# MotorSheet.net
KiCad netlist of a schematic drawn in Altium Designer
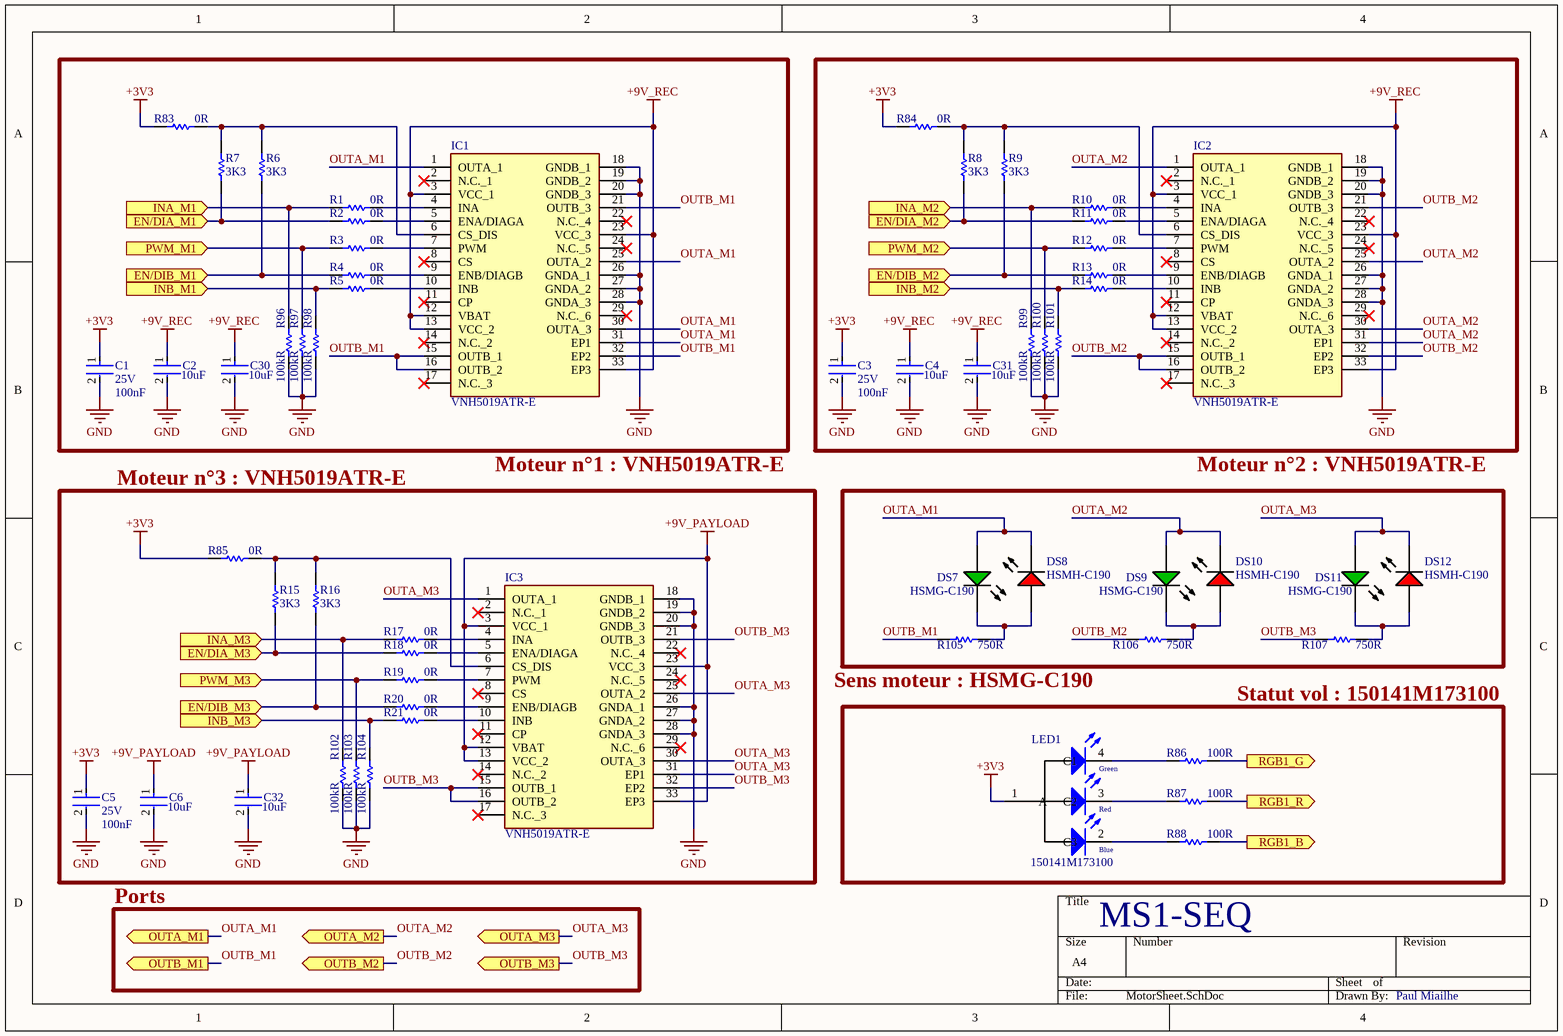
[diagram p0: MotorSheet.SchDoc]

(export (version "E")
  (design (tool "Eeschema 10.0.6"))
  (components
    (comp (ref "C1")
      (value "CGA3E2X7R1E104K080AA")
      (footprint "FP-CGA3E-0_3-0_1-MFG")
      (description "Cap Ceramic 100nF 25V X7R 10% Pad SMD 0603 +125°C Automotive T/R")
      (fields
        (field (name "VOLTAGE RATING (DC)") "25V")
        (field (name "CAPACITANCE") "100nF")
        (field (name "TOLERANCE") "10%")
        (field (name "MANUFACTURER") "TDK")
      )
      (libsource (lib "Altium Content Vault") (part "b4654b650e69147ec39a6b967a45e02"))
    )
    (comp (ref "C2")
      (value "GRM31CR71E106KA12L")
      (footprint "FP-GRM31C-0_2-e0_3_0_8-MFG")
      (description "Chip Multilayer Ceramic Capacitors for General Purpose, 1206, 10uF, X7R, 15%, 10%, 25V")
      (fields
        (field (name "TOLERANCE") "10%")
        (field (name "VOLTAGE") "25V")
        (field (name "CAPACITANCE") "10uF")
      )
      (libsource (lib "Altium Content Vault") (part "02cd4be3c70576c341d710602a673aa"))
    )
    (comp (ref "C3")
      (value "CGA3E2X7R1E104K080AA")
      (footprint "FP-CGA3E-0_3-0_1-MFG")
      (description "Cap Ceramic 100nF 25V X7R 10% Pad SMD 0603 +125°C Automotive T/R")
      (fields
        (field (name "VOLTAGE RATING (DC)") "25V")
        (field (name "CAPACITANCE") "100nF")
        (field (name "TOLERANCE") "10%")
        (field (name "MANUFACTURER") "TDK")
      )
      (libsource (lib "Altium Content Vault") (part "b4654b650e69147ec39a6b967a45e02"))
    )
    (comp (ref "C4")
      (value "GRM31CR71E106KA12L")
      (footprint "FP-GRM31C-0_2-e0_3_0_8-MFG")
      (description "Chip Multilayer Ceramic Capacitors for General Purpose, 1206, 10uF, X7R, 15%, 10%, 25V")
      (fields
        (field (name "TOLERANCE") "10%")
        (field (name "VOLTAGE") "25V")
        (field (name "CAPACITANCE") "10uF")
      )
      (libsource (lib "Altium Content Vault") (part "02cd4be3c70576c341d710602a673aa"))
    )
    (comp (ref "C5")
      (value "CGA3E2X7R1E104K080AA")
      (footprint "FP-CGA3E-0_3-0_1-MFG")
      (description "Cap Ceramic 100nF 25V X7R 10% Pad SMD 0603 +125°C Automotive T/R")
      (fields
        (field (name "VOLTAGE RATING (DC)") "25V")
        (field (name "CAPACITANCE") "100nF")
        (field (name "TOLERANCE") "10%")
        (field (name "MANUFACTURER") "TDK")
      )
      (libsource (lib "Altium Content Vault") (part "b4654b650e69147ec39a6b967a45e02"))
    )
    (comp (ref "C6")
      (value "GRM31CR71E106KA12L")
      (footprint "FP-GRM31C-0_2-e0_3_0_8-MFG")
      (description "Chip Multilayer Ceramic Capacitors for General Purpose, 1206, 10uF, X7R, 15%, 10%, 25V")
      (fields
        (field (name "TOLERANCE") "10%")
        (field (name "VOLTAGE") "25V")
        (field (name "CAPACITANCE") "10uF")
      )
      (libsource (lib "Altium Content Vault") (part "02cd4be3c70576c341d710602a673aa"))
    )
    (comp (ref "C30")
      (value "GRM31CR71E106KA12L")
      (footprint "FP-GRM31C-0_2-e0_3_0_8-MFG")
      (description "Chip Multilayer Ceramic Capacitors for General Purpose, 1206, 10uF, X7R, 15%, 10%, 25V")
      (fields
        (field (name "TOLERANCE") "10%")
        (field (name "VOLTAGE") "25V")
        (field (name "CAPACITANCE") "10uF")
      )
      (libsource (lib "Altium Content Vault") (part "02cd4be3c70576c341d710602a673aa"))
    )
    (comp (ref "C31")
      (value "GRM31CR71E106KA12L")
      (footprint "FP-GRM31C-0_2-e0_3_0_8-MFG")
      (description "Chip Multilayer Ceramic Capacitors for General Purpose, 1206, 10uF, X7R, 15%, 10%, 25V")
      (fields
        (field (name "TOLERANCE") "10%")
        (field (name "VOLTAGE") "25V")
        (field (name "CAPACITANCE") "10uF")
      )
      (libsource (lib "Altium Content Vault") (part "02cd4be3c70576c341d710602a673aa"))
    )
    (comp (ref "C32")
      (value "GRM31CR71E106KA12L")
      (footprint "FP-GRM31C-0_2-e0_3_0_8-MFG")
      (description "Chip Multilayer Ceramic Capacitors for General Purpose, 1206, 10uF, X7R, 15%, 10%, 25V")
      (fields
        (field (name "TOLERANCE") "10%")
        (field (name "VOLTAGE") "25V")
        (field (name "CAPACITANCE") "10uF")
      )
      (libsource (lib "Altium Content Vault") (part "02cd4be3c70576c341d710602a673aa"))
    )
    (comp (ref "DS7")
      (value "HSMG-C190")
      (footprint "AVAG-HSMX-C190_V")
      (description "Chip LED, Green, 2.2 V, -40 to 85 degC, 2-Pin SMD, RoHS, Tape and Reel")
      (libsource (lib "Altium Content Vault") (part "LED-GREEN-AK-2"))
    )
    (comp (ref "DS8")
      (value "HSMH-C190")
      (footprint "AVAG-HSMX-C190_V")
      (description "LED Uni-Color Red, 65 mW, 20 mA, -40 to 85 degC, 2-Pin SMD, RoHS, Tape and Reel")
      (libsource (lib "Altium Content Vault") (part "LED-RED-AK-2"))
    )
    (comp (ref "DS9")
      (value "HSMG-C190")
      (footprint "AVAG-HSMX-C190_V")
      (description "Chip LED, Green, 2.2 V, -40 to 85 degC, 2-Pin SMD, RoHS, Tape and Reel")
      (libsource (lib "Altium Content Vault") (part "LED-GREEN-AK-2"))
    )
    (comp (ref "DS10")
      (value "HSMH-C190")
      (footprint "AVAG-HSMX-C190_V")
      (description "LED Uni-Color Red, 65 mW, 20 mA, -40 to 85 degC, 2-Pin SMD, RoHS, Tape and Reel")
      (libsource (lib "Altium Content Vault") (part "LED-RED-AK-2"))
    )
    (comp (ref "DS11")
      (value "HSMG-C190")
      (footprint "AVAG-HSMX-C190_V")
      (description "Chip LED, Green, 2.2 V, -40 to 85 degC, 2-Pin SMD, RoHS, Tape and Reel")
      (libsource (lib "Altium Content Vault") (part "LED-GREEN-AK-2"))
    )
    (comp (ref "DS12")
      (value "HSMH-C190")
      (footprint "AVAG-HSMX-C190_V")
      (description "LED Uni-Color Red, 65 mW, 20 mA, -40 to 85 degC, 2-Pin SMD, RoHS, Tape and Reel")
      (libsource (lib "Altium Content Vault") (part "LED-RED-AK-2"))
    )
    (comp (ref "IC1")
      (value "VNH5019ATR-E")
      (footprint "SamacSys:VNH5019A-E_1")
      (description "Integrated Circuit")
      (fields (field (name "MOUSER PART NUMBER") "511-VNH5019ATR-E"))
      (libsource (lib "*") (part "VNH5019ATR-E"))
    )
    (comp (ref "IC2")
      (value "VNH5019ATR-E")
      (footprint "SamacSys:VNH5019A-E_1")
      (description "Integrated Circuit")
      (fields (field (name "MOUSER PART NUMBER") "511-VNH5019ATR-E"))
      (libsource (lib "*") (part "VNH5019ATR-E"))
    )
    (comp (ref "IC3")
      (value "VNH5019ATR-E")
      (footprint "SamacSys:VNH5019A-E_1")
      (description "Integrated Circuit")
      (fields (field (name "MOUSER PART NUMBER") "511-VNH5019ATR-E"))
      (libsource (lib "*") (part "VNH5019ATR-E"))
    )
    (comp (ref "LED1")
      (value "150141M173100")
      (footprint "3528_A")
      (description "SMD Full-Color Top LED, WL-SFTW, Red & Green & Blue")
      (fields (field (name "MANUFACTURER") "Wuerth Elektronik"))
      (libsource (lib "Altium Content Vault") (part "WE-LED_RGB_A1B2R3G4-4"))
    )
    (comp (ref "R1")
      (value "0R")
      (footprint "RESC1608X55X25ML10T15")
      (description "Chip Resistor, 0 Ohm, +/- 5%, 0.1 W, -55 to 155 degC, 0603 (1608 Metric), RoHS, Tape and Reel")
      (fields (field (name "TOLERANCE") "5%") (field (name "MANUFACTURER") "Yageo"))
      (libsource (lib "Altium Content Vault") (part "RES-2"))
    )
    (comp (ref "R2")
      (value "0R")
      (footprint "RESC1608X55X25ML10T15")
      (description "Chip Resistor, 0 Ohm, +/- 5%, 0.1 W, -55 to 155 degC, 0603 (1608 Metric), RoHS, Tape and Reel")
      (fields (field (name "TOLERANCE") "5%") (field (name "MANUFACTURER") "Yageo"))
      (libsource (lib "Altium Content Vault") (part "RES-2"))
    )
    (comp (ref "R3")
      (value "0R")
      (footprint "RESC1608X55X25ML10T15")
      (description "Chip Resistor, 0 Ohm, +/- 5%, 0.1 W, -55 to 155 degC, 0603 (1608 Metric), RoHS, Tape and Reel")
      (fields (field (name "TOLERANCE") "5%") (field (name "MANUFACTURER") "Yageo"))
      (libsource (lib "Altium Content Vault") (part "RES-2"))
    )
    (comp (ref "R4")
      (value "0R")
      (footprint "RESC1608X55X25ML10T15")
      (description "Chip Resistor, 0 Ohm, +/- 5%, 0.1 W, -55 to 155 degC, 0603 (1608 Metric), RoHS, Tape and Reel")
      (fields (field (name "TOLERANCE") "5%") (field (name "MANUFACTURER") "Yageo"))
      (libsource (lib "Altium Content Vault") (part "RES-2"))
    )
    (comp (ref "R5")
      (value "0R")
      (footprint "RESC1608X55X25ML10T15")
      (description "Chip Resistor, 0 Ohm, +/- 5%, 0.1 W, -55 to 155 degC, 0603 (1608 Metric), RoHS, Tape and Reel")
      (fields (field (name "TOLERANCE") "5%") (field (name "MANUFACTURER") "Yageo"))
      (libsource (lib "Altium Content Vault") (part "RES-2"))
    )
    (comp (ref "R6")
      (value "3K3")
      (footprint "RESC1608X55X25ML10T15")
      (description "Chip Resistor, 3.3 KOhm, +/- 1%, 0.1 W, -55 to 155 degC, 0603 (1608 Metric), RoHS, Tape and Reel")
      (fields (field (name "MANUFACTURER") "Yageo") (field (name "TOLERANCE") "1%"))
      (libsource (lib "Altium Content Vault") (part "RES-2"))
    )
    (comp (ref "R7")
      (value "3K3")
      (footprint "RESC1608X55X25ML10T15")
      (description "Chip Resistor, 3.3 KOhm, +/- 1%, 0.1 W, -55 to 155 degC, 0603 (1608 Metric), RoHS, Tape and Reel")
      (fields (field (name "MANUFACTURER") "Yageo") (field (name "TOLERANCE") "1%"))
      (libsource (lib "Altium Content Vault") (part "RES-2"))
    )
    (comp (ref "R8")
      (value "3K3")
      (footprint "RESC1608X55X25ML10T15")
      (description "Chip Resistor, 3.3 KOhm, +/- 1%, 0.1 W, -55 to 155 degC, 0603 (1608 Metric), RoHS, Tape and Reel")
      (fields (field (name "MANUFACTURER") "Yageo") (field (name "TOLERANCE") "1%"))
      (libsource (lib "Altium Content Vault") (part "RES-2"))
    )
    (comp (ref "R9")
      (value "3K3")
      (footprint "RESC1608X55X25ML10T15")
      (description "Chip Resistor, 3.3 KOhm, +/- 1%, 0.1 W, -55 to 155 degC, 0603 (1608 Metric), RoHS, Tape and Reel")
      (fields (field (name "MANUFACTURER") "Yageo") (field (name "TOLERANCE") "1%"))
      (libsource (lib "Altium Content Vault") (part "RES-2"))
    )
    (comp (ref "R10")
      (value "0R")
      (footprint "RESC1608X55X25ML10T15")
      (description "Chip Resistor, 0 Ohm, +/- 5%, 0.1 W, -55 to 155 degC, 0603 (1608 Metric), RoHS, Tape and Reel")
      (fields (field (name "TOLERANCE") "5%") (field (name "MANUFACTURER") "Yageo"))
      (libsource (lib "Altium Content Vault") (part "RES-2"))
    )
    (comp (ref "R11")
      (value "0R")
      (footprint "RESC1608X55X25ML10T15")
      (description "Chip Resistor, 0 Ohm, +/- 5%, 0.1 W, -55 to 155 degC, 0603 (1608 Metric), RoHS, Tape and Reel")
      (fields (field (name "TOLERANCE") "5%") (field (name "MANUFACTURER") "Yageo"))
      (libsource (lib "Altium Content Vault") (part "RES-2"))
    )
    (comp (ref "R12")
      (value "0R")
      (footprint "RESC1608X55X25ML10T15")
      (description "Chip Resistor, 0 Ohm, +/- 5%, 0.1 W, -55 to 155 degC, 0603 (1608 Metric), RoHS, Tape and Reel")
      (fields (field (name "TOLERANCE") "5%") (field (name "MANUFACTURER") "Yageo"))
      (libsource (lib "Altium Content Vault") (part "RES-2"))
    )
    (comp (ref "R13")
      (value "0R")
      (footprint "RESC1608X55X25ML10T15")
      (description "Chip Resistor, 0 Ohm, +/- 5%, 0.1 W, -55 to 155 degC, 0603 (1608 Metric), RoHS, Tape and Reel")
      (fields (field (name "TOLERANCE") "5%") (field (name "MANUFACTURER") "Yageo"))
      (libsource (lib "Altium Content Vault") (part "RES-2"))
    )
    (comp (ref "R14")
      (value "0R")
      (footprint "RESC1608X55X25ML10T15")
      (description "Chip Resistor, 0 Ohm, +/- 5%, 0.1 W, -55 to 155 degC, 0603 (1608 Metric), RoHS, Tape and Reel")
      (fields (field (name "TOLERANCE") "5%") (field (name "MANUFACTURER") "Yageo"))
      (libsource (lib "Altium Content Vault") (part "RES-2"))
    )
    (comp (ref "R15")
      (value "3K3")
      (footprint "RESC1608X55X25ML10T15")
      (description "Chip Resistor, 3.3 KOhm, +/- 1%, 0.1 W, -55 to 155 degC, 0603 (1608 Metric), RoHS, Tape and Reel")
      (fields (field (name "MANUFACTURER") "Yageo") (field (name "TOLERANCE") "1%"))
      (libsource (lib "Altium Content Vault") (part "RES-2"))
    )
    (comp (ref "R16")
      (value "3K3")
      (footprint "RESC1608X55X25ML10T15")
      (description "Chip Resistor, 3.3 KOhm, +/- 1%, 0.1 W, -55 to 155 degC, 0603 (1608 Metric), RoHS, Tape and Reel")
      (fields (field (name "MANUFACTURER") "Yageo") (field (name "TOLERANCE") "1%"))
      (libsource (lib "Altium Content Vault") (part "RES-2"))
    )
    (comp (ref "R17")
      (value "0R")
      (footprint "RESC1608X55X25ML10T15")
      (description "Chip Resistor, 0 Ohm, +/- 5%, 0.1 W, -55 to 155 degC, 0603 (1608 Metric), RoHS, Tape and Reel")
      (fields (field (name "TOLERANCE") "5%") (field (name "MANUFACTURER") "Yageo"))
      (libsource (lib "Altium Content Vault") (part "RES-2"))
    )
    (comp (ref "R18")
      (value "0R")
      (footprint "RESC1608X55X25ML10T15")
      (description "Chip Resistor, 0 Ohm, +/- 5%, 0.1 W, -55 to 155 degC, 0603 (1608 Metric), RoHS, Tape and Reel")
      (fields (field (name "TOLERANCE") "5%") (field (name "MANUFACTURER") "Yageo"))
      (libsource (lib "Altium Content Vault") (part "RES-2"))
    )
    (comp (ref "R19")
      (value "0R")
      (footprint "RESC1608X55X25ML10T15")
      (description "Chip Resistor, 0 Ohm, +/- 5%, 0.1 W, -55 to 155 degC, 0603 (1608 Metric), RoHS, Tape and Reel")
      (fields (field (name "TOLERANCE") "5%") (field (name "MANUFACTURER") "Yageo"))
      (libsource (lib "Altium Content Vault") (part "RES-2"))
    )
    (comp (ref "R20")
      (value "0R")
      (footprint "RESC1608X55X25ML10T15")
      (description "Chip Resistor, 0 Ohm, +/- 5%, 0.1 W, -55 to 155 degC, 0603 (1608 Metric), RoHS, Tape and Reel")
      (fields (field (name "TOLERANCE") "5%") (field (name "MANUFACTURER") "Yageo"))
      (libsource (lib "Altium Content Vault") (part "RES-2"))
    )
    (comp (ref "R21")
      (value "0R")
      (footprint "RESC1608X55X25ML10T15")
      (description "Chip Resistor, 0 Ohm, +/- 5%, 0.1 W, -55 to 155 degC, 0603 (1608 Metric), RoHS, Tape and Reel")
      (fields (field (name "TOLERANCE") "5%") (field (name "MANUFACTURER") "Yageo"))
      (libsource (lib "Altium Content Vault") (part "RES-2"))
    )
    (comp (ref "R83")
      (value "0R")
      (footprint "RESC1608X55X25ML10T15")
      (description "Chip Resistor, 0 Ohm, +/- 5%, 0.1 W, -55 to 155 degC, 0603 (1608 Metric), RoHS, Tape and Reel")
      (fields (field (name "TOLERANCE") "5%") (field (name "MANUFACTURER") "Yageo"))
      (libsource (lib "Altium Content Vault") (part "RES-2"))
    )
    (comp (ref "R84")
      (value "0R")
      (footprint "RESC1608X55X25ML10T15")
      (description "Chip Resistor, 0 Ohm, +/- 5%, 0.1 W, -55 to 155 degC, 0603 (1608 Metric), RoHS, Tape and Reel")
      (fields (field (name "TOLERANCE") "5%") (field (name "MANUFACTURER") "Yageo"))
      (libsource (lib "Altium Content Vault") (part "RES-2"))
    )
    (comp (ref "R85")
      (value "0R")
      (footprint "RESC1608X55X25ML10T15")
      (description "Chip Resistor, 0 Ohm, +/- 5%, 0.1 W, -55 to 155 degC, 0603 (1608 Metric), RoHS, Tape and Reel")
      (fields (field (name "TOLERANCE") "5%") (field (name "MANUFACTURER") "Yageo"))
      (libsource (lib "Altium Content Vault") (part "RES-2"))
    )
    (comp (ref "R86")
      (value "ERJ-3EKF1000V")
      (footprint "RESC1608X55X30LL15T15")
      (fields
        (field (name "MANUFACTURER") "Panasonic")
        (field (name "MANUFACTURER PART NUMBER") "ERJ3EKF1000V")
        (field (name "RESISTANCE") "100R")
        (field (name "TOLERANCE") "1%")
      )
      (libsource (lib "Altium Content Vault") (part "RES"))
    )
    (comp (ref "R87")
      (value "ERJ-3EKF1000V")
      (footprint "RESC1608X55X30LL15T15")
      (fields
        (field (name "MANUFACTURER") "Panasonic")
        (field (name "MANUFACTURER PART NUMBER") "ERJ3EKF1000V")
        (field (name "RESISTANCE") "100R")
        (field (name "TOLERANCE") "1%")
      )
      (libsource (lib "Altium Content Vault") (part "RES"))
    )
    (comp (ref "R88")
      (value "ERJ-3EKF1000V")
      (footprint "RESC1608X55X30LL15T15")
      (fields
        (field (name "MANUFACTURER") "Panasonic")
        (field (name "MANUFACTURER PART NUMBER") "ERJ3EKF1000V")
        (field (name "RESISTANCE") "100R")
        (field (name "TOLERANCE") "1%")
      )
      (libsource (lib "Altium Content Vault") (part "RES"))
    )
    (comp (ref "R96")
      (value "ERA3AEB104V")
      (footprint "RESC1608X55X30ML20T20")
      (fields
        (field (name "MANUFACTURER") "Panasonic")
        (field (name "MANUFACTURER PART NUMBER") "ERA-3AEB104V")
        (field (name "RESISTANCE") "100kR")
        (field (name "TOLERANCE") "0.1%")
      )
      (libsource (lib "Altium Content Vault") (part "RES"))
    )
    (comp (ref "R97")
      (value "ERA3AEB104V")
      (footprint "RESC1608X55X30ML20T20")
      (fields
        (field (name "MANUFACTURER") "Panasonic")
        (field (name "MANUFACTURER PART NUMBER") "ERA-3AEB104V")
        (field (name "RESISTANCE") "100kR")
        (field (name "TOLERANCE") "0.1%")
      )
      (libsource (lib "Altium Content Vault") (part "RES"))
    )
    (comp (ref "R98")
      (value "ERA3AEB104V")
      (footprint "RESC1608X55X30ML20T20")
      (fields
        (field (name "MANUFACTURER") "Panasonic")
        (field (name "MANUFACTURER PART NUMBER") "ERA-3AEB104V")
        (field (name "RESISTANCE") "100kR")
        (field (name "TOLERANCE") "0.1%")
      )
      (libsource (lib "Altium Content Vault") (part "RES"))
    )
    (comp (ref "R99")
      (value "ERA3AEB104V")
      (footprint "RESC1608X55X30ML20T20")
      (fields
        (field (name "MANUFACTURER") "Panasonic")
        (field (name "MANUFACTURER PART NUMBER") "ERA-3AEB104V")
        (field (name "RESISTANCE") "100kR")
        (field (name "TOLERANCE") "0.1%")
      )
      (libsource (lib "Altium Content Vault") (part "RES"))
    )
    (comp (ref "R100")
      (value "ERA3AEB104V")
      (footprint "RESC1608X55X30ML20T20")
      (fields
        (field (name "MANUFACTURER") "Panasonic")
        (field (name "MANUFACTURER PART NUMBER") "ERA-3AEB104V")
        (field (name "RESISTANCE") "100kR")
        (field (name "TOLERANCE") "0.1%")
      )
      (libsource (lib "Altium Content Vault") (part "RES"))
    )
    (comp (ref "R101")
      (value "ERA3AEB104V")
      (footprint "RESC1608X55X30ML20T20")
      (fields
        (field (name "MANUFACTURER") "Panasonic")
        (field (name "MANUFACTURER PART NUMBER") "ERA-3AEB104V")
        (field (name "RESISTANCE") "100kR")
        (field (name "TOLERANCE") "0.1%")
      )
      (libsource (lib "Altium Content Vault") (part "RES"))
    )
    (comp (ref "R102")
      (value "ERA3AEB104V")
      (footprint "RESC1608X55X30ML20T20")
      (fields
        (field (name "MANUFACTURER") "Panasonic")
        (field (name "MANUFACTURER PART NUMBER") "ERA-3AEB104V")
        (field (name "RESISTANCE") "100kR")
        (field (name "TOLERANCE") "0.1%")
      )
      (libsource (lib "Altium Content Vault") (part "RES"))
    )
    (comp (ref "R103")
      (value "ERA3AEB104V")
      (footprint "RESC1608X55X30ML20T20")
      (fields
        (field (name "MANUFACTURER") "Panasonic")
        (field (name "MANUFACTURER PART NUMBER") "ERA-3AEB104V")
        (field (name "RESISTANCE") "100kR")
        (field (name "TOLERANCE") "0.1%")
      )
      (libsource (lib "Altium Content Vault") (part "RES"))
    )
    (comp (ref "R104")
      (value "ERA3AEB104V")
      (footprint "RESC1608X55X30ML20T20")
      (fields
        (field (name "MANUFACTURER") "Panasonic")
        (field (name "MANUFACTURER PART NUMBER") "ERA-3AEB104V")
        (field (name "RESISTANCE") "100kR")
        (field (name "TOLERANCE") "0.1%")
      )
      (libsource (lib "Altium Content Vault") (part "RES"))
    )
    (comp (ref "R105")
      (value "ERA-3AEB751V")
      (footprint "RESC1608X55X30ML20T20")
      (fields
        (field (name "MANUFACTURER") "Panasonic")
        (field (name "TOLERANCE") "0.1%")
        (field (name "RESISTANCE") "750R")
      )
      (libsource (lib "Altium Content Vault") (part "RES"))
    )
    (comp (ref "R106")
      (value "ERA-3AEB751V")
      (footprint "RESC1608X55X30ML20T20")
      (fields
        (field (name "MANUFACTURER") "Panasonic")
        (field (name "TOLERANCE") "0.1%")
        (field (name "RESISTANCE") "750R")
      )
      (libsource (lib "Altium Content Vault") (part "RES"))
    )
    (comp (ref "R107")
      (value "ERA-3AEB751V")
      (footprint "RESC1608X55X30ML20T20")
      (fields
        (field (name "MANUFACTURER") "Panasonic")
        (field (name "TOLERANCE") "0.1%")
        (field (name "RESISTANCE") "750R")
      )
      (libsource (lib "Altium Content Vault") (part "RES"))
    )
  )
  (nets
    (net (code "1") (name "+3V3") (class "Default")
      (node (ref "C1") (pin "1") (pinfunction "1_1") (pintype "passive"))
      (node (ref "C3") (pin "1") (pinfunction "1_1") (pintype "passive"))
      (node (ref "C5") (pin "1") (pinfunction "1_1") (pintype "passive"))
      (node (ref "LED1") (pin "1") (pinfunction "A_1") (pintype "passive"))
      (node (ref "R83") (pin "1") (pinfunction "1_1") (pintype "passive"))
      (node (ref "R84") (pin "1") (pinfunction "1_1") (pintype "passive"))
      (node (ref "R85") (pin "1") (pinfunction "1_1") (pintype "passive"))
    )
    (net (code "2") (name "+9V_PAYLOAD") (class "Default")
      (node (ref "C32") (pin "1") (pinfunction "1_1") (pintype "passive"))
      (node (ref "C6") (pin "1") (pinfunction "1_1") (pintype "passive"))
      (node (ref "IC3") (pin "12") (pinfunction "VBAT_12") (pintype "passive"))
      (node (ref "IC3") (pin "13") (pinfunction "VCC_2_13") (pintype "passive"))
      (node (ref "IC3") (pin "23") (pinfunction "VCC_3_23") (pintype "passive"))
      (node (ref "IC3") (pin "3") (pinfunction "VCC_1_3") (pintype "passive"))
      (node (ref "IC3") (pin "33") (pinfunction "EP3_33") (pintype "passive"))
    )
    (net (code "3") (name "+9V_REC") (class "Default")
      (node (ref "C2") (pin "1") (pinfunction "1_1") (pintype "passive"))
      (node (ref "C30") (pin "1") (pinfunction "1_1") (pintype "passive"))
      (node (ref "C31") (pin "1") (pinfunction "1_1") (pintype "passive"))
      (node (ref "C4") (pin "1") (pinfunction "1_1") (pintype "passive"))
      (node (ref "IC1") (pin "12") (pinfunction "VBAT_12") (pintype "passive"))
      (node (ref "IC1") (pin "13") (pinfunction "VCC_2_13") (pintype "passive"))
      (node (ref "IC1") (pin "23") (pinfunction "VCC_3_23") (pintype "passive"))
      (node (ref "IC1") (pin "3") (pinfunction "VCC_1_3") (pintype "passive"))
      (node (ref "IC1") (pin "33") (pinfunction "EP3_33") (pintype "passive"))
      (node (ref "IC2") (pin "12") (pinfunction "VBAT_12") (pintype "passive"))
      (node (ref "IC2") (pin "13") (pinfunction "VCC_2_13") (pintype "passive"))
      (node (ref "IC2") (pin "23") (pinfunction "VCC_3_23") (pintype "passive"))
      (node (ref "IC2") (pin "3") (pinfunction "VCC_1_3") (pintype "passive"))
      (node (ref "IC2") (pin "33") (pinfunction "EP3_33") (pintype "passive"))
    )
    (net (code "4") (name "/EN{slash}DIA_M1") (class "Default")
      (node (ref "R2") (pin "1") (pinfunction "1_1") (pintype "passive"))
      (node (ref "R7") (pin "1") (pinfunction "1_1") (pintype "passive"))
    )
    (net (code "5") (name "/EN{slash}DIA_M2") (class "Default")
      (node (ref "R11") (pin "1") (pinfunction "1_1") (pintype "passive"))
      (node (ref "R8") (pin "1") (pinfunction "1_1") (pintype "passive"))
    )
    (net (code "6") (name "/EN{slash}DIA_M3") (class "Default")
      (node (ref "R15") (pin "1") (pinfunction "1_1") (pintype "passive"))
      (node (ref "R18") (pin "1") (pinfunction "1_1") (pintype "passive"))
    )
    (net (code "7") (name "/EN{slash}DIB_M1") (class "Default")
      (node (ref "R4") (pin "1") (pinfunction "1_1") (pintype "passive"))
      (node (ref "R6") (pin "1") (pinfunction "1_1") (pintype "passive"))
    )
    (net (code "8") (name "/EN{slash}DIB_M2") (class "Default")
      (node (ref "R13") (pin "1") (pinfunction "1_1") (pintype "passive"))
      (node (ref "R9") (pin "1") (pinfunction "1_1") (pintype "passive"))
    )
    (net (code "9") (name "/EN{slash}DIB_M3") (class "Default")
      (node (ref "R16") (pin "1") (pinfunction "1_1") (pintype "passive"))
      (node (ref "R20") (pin "1") (pinfunction "1_1") (pintype "passive"))
    )
    (net (code "10") (name "/INA_M1") (class "Default")
      (node (ref "R1") (pin "1") (pinfunction "1_1") (pintype "passive"))
      (node (ref "R96") (pin "2") (pinfunction "2_2") (pintype "passive"))
    )
    (net (code "11") (name "/INA_M2") (class "Default")
      (node (ref "R10") (pin "1") (pinfunction "1_1") (pintype "passive"))
      (node (ref "R99") (pin "2") (pinfunction "2_2") (pintype "passive"))
    )
    (net (code "12") (name "/INA_M3") (class "Default")
      (node (ref "R102") (pin "2") (pinfunction "2_2") (pintype "passive"))
      (node (ref "R17") (pin "1") (pinfunction "1_1") (pintype "passive"))
    )
    (net (code "13") (name "/INB_M1") (class "Default")
      (node (ref "R5") (pin "1") (pinfunction "1_1") (pintype "passive"))
      (node (ref "R98") (pin "2") (pinfunction "2_2") (pintype "passive"))
    )
    (net (code "14") (name "/INB_M2") (class "Default")
      (node (ref "R101") (pin "2") (pinfunction "2_2") (pintype "passive"))
      (node (ref "R14") (pin "1") (pinfunction "1_1") (pintype "passive"))
    )
    (net (code "15") (name "/INB_M3") (class "Default")
      (node (ref "R104") (pin "2") (pinfunction "2_2") (pintype "passive"))
      (node (ref "R21") (pin "1") (pinfunction "1_1") (pintype "passive"))
    )
    (net (code "16") (name "/OUTA_M1") (class "Default")
      (node (ref "DS7") (pin "1") (pinfunction "A_1") (pintype "passive"))
      (node (ref "DS8") (pin "2") (pinfunction "K_2") (pintype "passive"))
      (node (ref "IC1") (pin "1") (pinfunction "OUTA_1_1") (pintype "passive"))
      (node (ref "IC1") (pin "25") (pinfunction "OUTA_2_25") (pintype "passive"))
      (node (ref "IC1") (pin "30") (pinfunction "OUTA_3_30") (pintype "passive"))
      (node (ref "IC1") (pin "31") (pinfunction "EP1_31") (pintype "passive"))
    )
    (net (code "17") (name "/OUTA_M2") (class "Default")
      (node (ref "DS10") (pin "2") (pinfunction "K_2") (pintype "passive"))
      (node (ref "DS9") (pin "1") (pinfunction "A_1") (pintype "passive"))
      (node (ref "IC2") (pin "1") (pinfunction "OUTA_1_1") (pintype "passive"))
      (node (ref "IC2") (pin "25") (pinfunction "OUTA_2_25") (pintype "passive"))
      (node (ref "IC2") (pin "30") (pinfunction "OUTA_3_30") (pintype "passive"))
      (node (ref "IC2") (pin "31") (pinfunction "EP1_31") (pintype "passive"))
    )
    (net (code "18") (name "/OUTA_M3") (class "Default")
      (node (ref "DS11") (pin "1") (pinfunction "A_1") (pintype "passive"))
      (node (ref "DS12") (pin "2") (pinfunction "K_2") (pintype "passive"))
      (node (ref "IC3") (pin "1") (pinfunction "OUTA_1_1") (pintype "passive"))
      (node (ref "IC3") (pin "25") (pinfunction "OUTA_2_25") (pintype "passive"))
      (node (ref "IC3") (pin "30") (pinfunction "OUTA_3_30") (pintype "passive"))
      (node (ref "IC3") (pin "31") (pinfunction "EP1_31") (pintype "passive"))
    )
    (net (code "19") (name "/OUTB_M1") (class "Default")
      (node (ref "IC1") (pin "15") (pinfunction "OUTB_1_15") (pintype "passive"))
      (node (ref "IC1") (pin "16") (pinfunction "OUTB_2_16") (pintype "passive"))
      (node (ref "IC1") (pin "21") (pinfunction "OUTB_3_21") (pintype "passive"))
      (node (ref "IC1") (pin "32") (pinfunction "EP2_32") (pintype "passive"))
      (node (ref "R105") (pin "1") (pinfunction "1_1") (pintype "passive"))
    )
    (net (code "20") (name "/OUTB_M2") (class "Default")
      (node (ref "IC2") (pin "15") (pinfunction "OUTB_1_15") (pintype "passive"))
      (node (ref "IC2") (pin "16") (pinfunction "OUTB_2_16") (pintype "passive"))
      (node (ref "IC2") (pin "21") (pinfunction "OUTB_3_21") (pintype "passive"))
      (node (ref "IC2") (pin "32") (pinfunction "EP2_32") (pintype "passive"))
      (node (ref "R106") (pin "1") (pinfunction "1_1") (pintype "passive"))
    )
    (net (code "21") (name "/OUTB_M3") (class "Default")
      (node (ref "IC3") (pin "15") (pinfunction "OUTB_1_15") (pintype "passive"))
      (node (ref "IC3") (pin "16") (pinfunction "OUTB_2_16") (pintype "passive"))
      (node (ref "IC3") (pin "21") (pinfunction "OUTB_3_21") (pintype "passive"))
      (node (ref "IC3") (pin "32") (pinfunction "EP2_32") (pintype "passive"))
      (node (ref "R107") (pin "1") (pinfunction "1_1") (pintype "passive"))
    )
    (net (code "22") (name "/PWM_M1") (class "Default")
      (node (ref "R3") (pin "1") (pinfunction "1_1") (pintype "passive"))
      (node (ref "R97") (pin "2") (pinfunction "2_2") (pintype "passive"))
    )
    (net (code "23") (name "/PWM_M2") (class "Default")
      (node (ref "R100") (pin "2") (pinfunction "2_2") (pintype "passive"))
      (node (ref "R12") (pin "1") (pinfunction "1_1") (pintype "passive"))
    )
    (net (code "24") (name "/PWM_M3") (class "Default")
      (node (ref "R103") (pin "2") (pinfunction "2_2") (pintype "passive"))
      (node (ref "R19") (pin "1") (pinfunction "1_1") (pintype "passive"))
    )
    (net (code "25") (name "/RGB1_B") (class "Default")
      (node (ref "R88") (pin "1") (pinfunction "1_1") (pintype "passive"))
    )
    (net (code "26") (name "/RGB1_G") (class "Default")
      (node (ref "R86") (pin "1") (pinfunction "1_1") (pintype "passive"))
    )
    (net (code "27") (name "/RGB1_R") (class "Default")
      (node (ref "R87") (pin "1") (pinfunction "1_1") (pintype "passive"))
    )
    (net (code "28") (name "GND") (class "Default")
      (node (ref "C1") (pin "2") (pinfunction "2_2") (pintype "passive"))
      (node (ref "C2") (pin "2") (pinfunction "2_2") (pintype "passive"))
      (node (ref "C3") (pin "2") (pinfunction "2_2") (pintype "passive"))
      (node (ref "C30") (pin "2") (pinfunction "2_2") (pintype "passive"))
      (node (ref "C31") (pin "2") (pinfunction "2_2") (pintype "passive"))
      (node (ref "C32") (pin "2") (pinfunction "2_2") (pintype "passive"))
      (node (ref "C4") (pin "2") (pinfunction "2_2") (pintype "passive"))
      (node (ref "C5") (pin "2") (pinfunction "2_2") (pintype "passive"))
      (node (ref "C6") (pin "2") (pinfunction "2_2") (pintype "passive"))
      (node (ref "IC1") (pin "18") (pinfunction "GNDB_1_18") (pintype "passive"))
      (node (ref "IC1") (pin "19") (pinfunction "GNDB_2_19") (pintype "passive"))
      (node (ref "IC1") (pin "20") (pinfunction "GNDB_3_20") (pintype "passive"))
      (node (ref "IC1") (pin "26") (pinfunction "GNDA_1_26") (pintype "passive"))
      (node (ref "IC1") (pin "27") (pinfunction "GNDA_2_27") (pintype "passive"))
      (node (ref "IC1") (pin "28") (pinfunction "GNDA_3_28") (pintype "passive"))
      (node (ref "IC2") (pin "18") (pinfunction "GNDB_1_18") (pintype "passive"))
      (node (ref "IC2") (pin "19") (pinfunction "GNDB_2_19") (pintype "passive"))
      (node (ref "IC2") (pin "20") (pinfunction "GNDB_3_20") (pintype "passive"))
      (node (ref "IC2") (pin "26") (pinfunction "GNDA_1_26") (pintype "passive"))
      (node (ref "IC2") (pin "27") (pinfunction "GNDA_2_27") (pintype "passive"))
      (node (ref "IC2") (pin "28") (pinfunction "GNDA_3_28") (pintype "passive"))
      (node (ref "IC3") (pin "18") (pinfunction "GNDB_1_18") (pintype "passive"))
      (node (ref "IC3") (pin "19") (pinfunction "GNDB_2_19") (pintype "passive"))
      (node (ref "IC3") (pin "20") (pinfunction "GNDB_3_20") (pintype "passive"))
      (node (ref "IC3") (pin "26") (pinfunction "GNDA_1_26") (pintype "passive"))
      (node (ref "IC3") (pin "27") (pinfunction "GNDA_2_27") (pintype "passive"))
      (node (ref "IC3") (pin "28") (pinfunction "GNDA_3_28") (pintype "passive"))
      (node (ref "R100") (pin "1") (pinfunction "1_1") (pintype "passive"))
      (node (ref "R101") (pin "1") (pinfunction "1_1") (pintype "passive"))
      (node (ref "R102") (pin "1") (pinfunction "1_1") (pintype "passive"))
      (node (ref "R103") (pin "1") (pinfunction "1_1") (pintype "passive"))
      (node (ref "R104") (pin "1") (pinfunction "1_1") (pintype "passive"))
      (node (ref "R96") (pin "1") (pinfunction "1_1") (pintype "passive"))
      (node (ref "R97") (pin "1") (pinfunction "1_1") (pintype "passive"))
      (node (ref "R98") (pin "1") (pinfunction "1_1") (pintype "passive"))
      (node (ref "R99") (pin "1") (pinfunction "1_1") (pintype "passive"))
    )
    (net (code "29") (name "Net-(DS7-K)") (class "Default")
      (node (ref "DS7") (pin "2") (pinfunction "K_2") (pintype "passive"))
      (node (ref "DS8") (pin "1") (pinfunction "A_1") (pintype "passive"))
      (node (ref "R105") (pin "2") (pinfunction "2_2") (pintype "passive"))
    )
    (net (code "30") (name "Net-(DS10-A)") (class "Default")
      (node (ref "DS10") (pin "1") (pinfunction "A_1") (pintype "passive"))
      (node (ref "DS9") (pin "2") (pinfunction "K_2") (pintype "passive"))
      (node (ref "R106") (pin "2") (pinfunction "2_2") (pintype "passive"))
    )
    (net (code "31") (name "Net-(DS11-K)") (class "Default")
      (node (ref "DS11") (pin "2") (pinfunction "K_2") (pintype "passive"))
      (node (ref "DS12") (pin "1") (pinfunction "A_1") (pintype "passive"))
      (node (ref "R107") (pin "2") (pinfunction "2_2") (pintype "passive"))
    )
    (net (code "32") (name "Net-(IC1-CS_DIS)") (class "Default")
      (node (ref "IC1") (pin "6") (pinfunction "CS_DIS_6") (pintype "passive"))
      (node (ref "R6") (pin "2") (pinfunction "2_2") (pintype "passive"))
      (node (ref "R7") (pin "2") (pinfunction "2_2") (pintype "passive"))
      (node (ref "R83") (pin "2") (pinfunction "2_2") (pintype "passive"))
    )
    (net (code "33") (name "Net-(IC1-ENA{slash}DIAGA)") (class "Default")
      (node (ref "IC1") (pin "5") (pinfunction "ENA/DIAGA_5") (pintype "passive"))
      (node (ref "R2") (pin "2") (pinfunction "2_2") (pintype "passive"))
    )
    (net (code "34") (name "Net-(IC1-ENB{slash}DIAGB)") (class "Default")
      (node (ref "IC1") (pin "9") (pinfunction "ENB/DIAGB_9") (pintype "passive"))
      (node (ref "R4") (pin "2") (pinfunction "2_2") (pintype "passive"))
    )
    (net (code "35") (name "Net-(IC1-INA)") (class "Default")
      (node (ref "IC1") (pin "4") (pinfunction "INA_4") (pintype "passive"))
      (node (ref "R1") (pin "2") (pinfunction "2_2") (pintype "passive"))
    )
    (net (code "36") (name "Net-(IC1-INB)") (class "Default")
      (node (ref "IC1") (pin "10") (pinfunction "INB_10") (pintype "passive"))
      (node (ref "R5") (pin "2") (pinfunction "2_2") (pintype "passive"))
    )
    (net (code "37") (name "Net-(IC1-PWM)") (class "Default")
      (node (ref "IC1") (pin "7") (pinfunction "PWM_7") (pintype "passive"))
      (node (ref "R3") (pin "2") (pinfunction "2_2") (pintype "passive"))
    )
    (net (code "38") (name "Net-(IC2-CS_DIS)") (class "Default")
      (node (ref "IC2") (pin "6") (pinfunction "CS_DIS_6") (pintype "passive"))
      (node (ref "R8") (pin "2") (pinfunction "2_2") (pintype "passive"))
      (node (ref "R84") (pin "2") (pinfunction "2_2") (pintype "passive"))
      (node (ref "R9") (pin "2") (pinfunction "2_2") (pintype "passive"))
    )
    (net (code "39") (name "Net-(IC2-ENA{slash}DIAGA)") (class "Default")
      (node (ref "IC2") (pin "5") (pinfunction "ENA/DIAGA_5") (pintype "passive"))
      (node (ref "R11") (pin "2") (pinfunction "2_2") (pintype "passive"))
    )
    (net (code "40") (name "Net-(IC2-ENB{slash}DIAGB)") (class "Default")
      (node (ref "IC2") (pin "9") (pinfunction "ENB/DIAGB_9") (pintype "passive"))
      (node (ref "R13") (pin "2") (pinfunction "2_2") (pintype "passive"))
    )
    (net (code "41") (name "Net-(IC2-INA)") (class "Default")
      (node (ref "IC2") (pin "4") (pinfunction "INA_4") (pintype "passive"))
      (node (ref "R10") (pin "2") (pinfunction "2_2") (pintype "passive"))
    )
    (net (code "42") (name "Net-(IC2-INB)") (class "Default")
      (node (ref "IC2") (pin "10") (pinfunction "INB_10") (pintype "passive"))
      (node (ref "R14") (pin "2") (pinfunction "2_2") (pintype "passive"))
    )
    (net (code "43") (name "Net-(IC2-PWM)") (class "Default")
      (node (ref "IC2") (pin "7") (pinfunction "PWM_7") (pintype "passive"))
      (node (ref "R12") (pin "2") (pinfunction "2_2") (pintype "passive"))
    )
    (net (code "44") (name "Net-(IC3-CS_DIS)") (class "Default")
      (node (ref "IC3") (pin "6") (pinfunction "CS_DIS_6") (pintype "passive"))
      (node (ref "R15") (pin "2") (pinfunction "2_2") (pintype "passive"))
      (node (ref "R16") (pin "2") (pinfunction "2_2") (pintype "passive"))
      (node (ref "R85") (pin "2") (pinfunction "2_2") (pintype "passive"))
    )
    (net (code "45") (name "Net-(IC3-ENA{slash}DIAGA)") (class "Default")
      (node (ref "IC3") (pin "5") (pinfunction "ENA/DIAGA_5") (pintype "passive"))
      (node (ref "R18") (pin "2") (pinfunction "2_2") (pintype "passive"))
    )
    (net (code "46") (name "Net-(IC3-ENB{slash}DIAGB)") (class "Default")
      (node (ref "IC3") (pin "9") (pinfunction "ENB/DIAGB_9") (pintype "passive"))
      (node (ref "R20") (pin "2") (pinfunction "2_2") (pintype "passive"))
    )
    (net (code "47") (name "Net-(IC3-INA)") (class "Default")
      (node (ref "IC3") (pin "4") (pinfunction "INA_4") (pintype "passive"))
      (node (ref "R17") (pin "2") (pinfunction "2_2") (pintype "passive"))
    )
    (net (code "48") (name "Net-(IC3-INB)") (class "Default")
      (node (ref "IC3") (pin "10") (pinfunction "INB_10") (pintype "passive"))
      (node (ref "R21") (pin "2") (pinfunction "2_2") (pintype "passive"))
    )
    (net (code "49") (name "Net-(IC3-PWM)") (class "Default")
      (node (ref "IC3") (pin "7") (pinfunction "PWM_7") (pintype "passive"))
      (node (ref "R19") (pin "2") (pinfunction "2_2") (pintype "passive"))
    )
    (net (code "50") (name "Net-(LED1-C1)") (class "Default")
      (node (ref "LED1") (pin "4") (pinfunction "C1_4") (pintype "passive"))
      (node (ref "R86") (pin "2") (pinfunction "2_2") (pintype "passive"))
    )
    (net (code "51") (name "Net-(LED1-C2)") (class "Default")
      (node (ref "LED1") (pin "3") (pinfunction "C2_3") (pintype "passive"))
      (node (ref "R87") (pin "2") (pinfunction "2_2") (pintype "passive"))
    )
    (net (code "52") (name "Net-(LED1-C3)") (class "Default")
      (node (ref "LED1") (pin "2") (pinfunction "C3_2") (pintype "passive"))
      (node (ref "R88") (pin "2") (pinfunction "2_2") (pintype "passive"))
    )
    (net (code "53") (name "unconnected-(IC1-CP-Pad11)") (class "Default")
      (node (ref "IC1") (pin "11") (pinfunction "CP_11") (pintype "passive+no_connect"))
    )
    (net (code "54") (name "unconnected-(IC1-CS-Pad8)") (class "Default")
      (node (ref "IC1") (pin "8") (pinfunction "CS_8") (pintype "passive+no_connect"))
    )
    (net (code "55") (name "unconnected-(IC1-N.C._1-Pad2)") (class "Default")
      (node (ref "IC1") (pin "2") (pinfunction "N.C._1_2") (pintype "passive+no_connect"))
    )
    (net (code "56") (name "unconnected-(IC1-N.C._2-Pad14)") (class "Default")
      (node (ref "IC1") (pin "14") (pinfunction "N.C._2_14") (pintype "passive+no_connect"))
    )
    (net (code "57") (name "unconnected-(IC1-N.C._3-Pad17)") (class "Default")
      (node (ref "IC1") (pin "17") (pinfunction "N.C._3_17") (pintype "passive+no_connect"))
    )
    (net (code "58") (name "unconnected-(IC1-N.C._4-Pad22)") (class "Default")
      (node (ref "IC1") (pin "22") (pinfunction "N.C._4_22") (pintype "passive+no_connect"))
    )
    (net (code "59") (name "unconnected-(IC1-N.C._5-Pad24)") (class "Default")
      (node (ref "IC1") (pin "24") (pinfunction "N.C._5_24") (pintype "passive+no_connect"))
    )
    (net (code "60") (name "unconnected-(IC1-N.C._6-Pad29)") (class "Default")
      (node (ref "IC1") (pin "29") (pinfunction "N.C._6_29") (pintype "passive+no_connect"))
    )
    (net (code "61") (name "unconnected-(IC2-CP-Pad11)") (class "Default")
      (node (ref "IC2") (pin "11") (pinfunction "CP_11") (pintype "passive+no_connect"))
    )
    (net (code "62") (name "unconnected-(IC2-CS-Pad8)") (class "Default")
      (node (ref "IC2") (pin "8") (pinfunction "CS_8") (pintype "passive+no_connect"))
    )
    (net (code "63") (name "unconnected-(IC2-N.C._1-Pad2)") (class "Default")
      (node (ref "IC2") (pin "2") (pinfunction "N.C._1_2") (pintype "passive+no_connect"))
    )
    (net (code "64") (name "unconnected-(IC2-N.C._2-Pad14)") (class "Default")
      (node (ref "IC2") (pin "14") (pinfunction "N.C._2_14") (pintype "passive+no_connect"))
    )
    (net (code "65") (name "unconnected-(IC2-N.C._3-Pad17)") (class "Default")
      (node (ref "IC2") (pin "17") (pinfunction "N.C._3_17") (pintype "passive+no_connect"))
    )
    (net (code "66") (name "unconnected-(IC2-N.C._4-Pad22)") (class "Default")
      (node (ref "IC2") (pin "22") (pinfunction "N.C._4_22") (pintype "passive+no_connect"))
    )
    (net (code "67") (name "unconnected-(IC2-N.C._5-Pad24)") (class "Default")
      (node (ref "IC2") (pin "24") (pinfunction "N.C._5_24") (pintype "passive+no_connect"))
    )
    (net (code "68") (name "unconnected-(IC2-N.C._6-Pad29)") (class "Default")
      (node (ref "IC2") (pin "29") (pinfunction "N.C._6_29") (pintype "passive+no_connect"))
    )
    (net (code "69") (name "unconnected-(IC3-CP-Pad11)") (class "Default")
      (node (ref "IC3") (pin "11") (pinfunction "CP_11") (pintype "passive+no_connect"))
    )
    (net (code "70") (name "unconnected-(IC3-CS-Pad8)") (class "Default")
      (node (ref "IC3") (pin "8") (pinfunction "CS_8") (pintype "passive+no_connect"))
    )
    (net (code "71") (name "unconnected-(IC3-N.C._1-Pad2)") (class "Default")
      (node (ref "IC3") (pin "2") (pinfunction "N.C._1_2") (pintype "passive+no_connect"))
    )
    (net (code "72") (name "unconnected-(IC3-N.C._2-Pad14)") (class "Default")
      (node (ref "IC3") (pin "14") (pinfunction "N.C._2_14") (pintype "passive+no_connect"))
    )
    (net (code "73") (name "unconnected-(IC3-N.C._3-Pad17)") (class "Default")
      (node (ref "IC3") (pin "17") (pinfunction "N.C._3_17") (pintype "passive+no_connect"))
    )
    (net (code "74") (name "unconnected-(IC3-N.C._4-Pad22)") (class "Default")
      (node (ref "IC3") (pin "22") (pinfunction "N.C._4_22") (pintype "passive+no_connect"))
    )
    (net (code "75") (name "unconnected-(IC3-N.C._5-Pad24)") (class "Default")
      (node (ref "IC3") (pin "24") (pinfunction "N.C._5_24") (pintype "passive+no_connect"))
    )
    (net (code "76") (name "unconnected-(IC3-N.C._6-Pad29)") (class "Default")
      (node (ref "IC3") (pin "29") (pinfunction "N.C._6_29") (pintype "passive+no_connect"))
    )
  )
)
